# AC_v40.net
KiCad netlist of a schematic drawn in Altium Designer
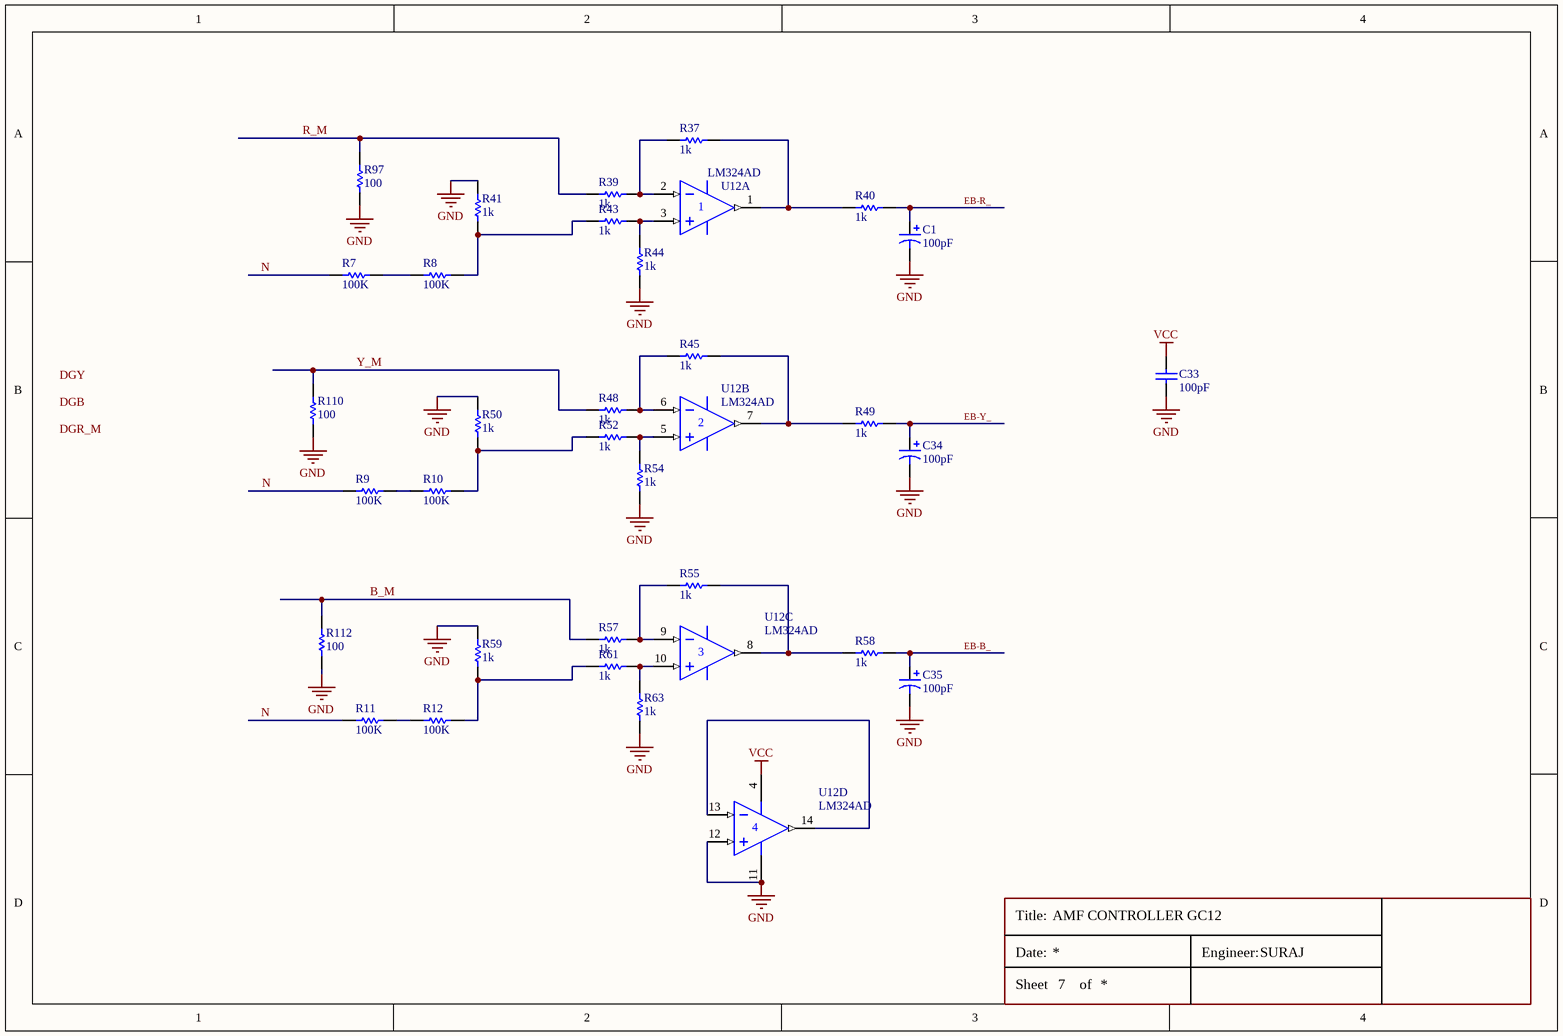
[diagram p0: AC_v40.SchDoc]

(export (version "E")
  (design (tool "Eeschema 10.0.6"))
  (components
    (comp (ref "C1")
      (value "100pF")
      (footprint "C1206")
      (description "Polarized Capacitor (Radial)")
      (fields (field (name "Comment") "10uF/63V") (field (name "PUBLISHER") "Altium Limited"))
      (libsource (lib "Miscellaneous Devices") (part "Cap Pol1"))
    )
    (comp (ref "C33")
      (value "100pF")
      (footprint "C1206")
      (description "Capacitor")
      (fields (field (name "Comment") ".1uF 1206") (field (name "PUBLISHER") "Altium Limited"))
      (libsource (lib "Miscellaneous Devices") (part "Cap"))
    )
    (comp (ref "C34")
      (value "100pF")
      (footprint "C1206")
      (description "Polarized Capacitor (Radial)")
      (fields (field (name "Comment") "10uF/63V") (field (name "PUBLISHER") "Altium Limited"))
      (libsource (lib "Miscellaneous Devices") (part "Cap Pol1"))
    )
    (comp (ref "C35")
      (value "100pF")
      (footprint "C1206")
      (description "Polarized Capacitor (Radial)")
      (fields (field (name "Comment") "10uF/63V") (field (name "PUBLISHER") "Altium Limited"))
      (libsource (lib "Miscellaneous Devices") (part "Cap Pol1"))
    )
    (comp (ref "R7")
      (value "100K")
      (footprint "AXIAL-0.5")
      (description "Semiconductor Resistor")
      (fields (field (name "Comment") "MFR 1M .5W") (field (name "PUBLISHER") "Altium Limited"))
      (libsource (lib "Miscellaneous Devices") (part "Res Semi"))
    )
    (comp (ref "R8")
      (value "100K")
      (footprint "AXIAL-0.5")
      (description "Semiconductor Resistor")
      (fields (field (name "Comment") "MFR 1M .5W") (field (name "PUBLISHER") "Altium Limited"))
      (libsource (lib "Miscellaneous Devices") (part "Res Semi"))
    )
    (comp (ref "R9")
      (value "100K")
      (footprint "AXIAL-0.5")
      (description "Semiconductor Resistor")
      (fields (field (name "Comment") "MFR 1M .5W") (field (name "PUBLISHER") "Altium Limited"))
      (libsource (lib "Miscellaneous Devices") (part "Res Semi"))
    )
    (comp (ref "R10")
      (value "100K")
      (footprint "AXIAL-0.5")
      (description "Semiconductor Resistor")
      (fields (field (name "Comment") "MFR 1M .5W") (field (name "PUBLISHER") "Altium Limited"))
      (libsource (lib "Miscellaneous Devices") (part "Res Semi"))
    )
    (comp (ref "R11")
      (value "100K")
      (footprint "AXIAL-0.5")
      (description "Semiconductor Resistor")
      (fields (field (name "Comment") "MFR 1M .5W") (field (name "PUBLISHER") "Altium Limited"))
      (libsource (lib "Miscellaneous Devices") (part "Res Semi"))
    )
    (comp (ref "R12")
      (value "100K")
      (footprint "AXIAL-0.5")
      (description "Semiconductor Resistor")
      (fields (field (name "Comment") "MFR 1M .5W") (field (name "PUBLISHER") "Altium Limited"))
      (libsource (lib "Miscellaneous Devices") (part "Res Semi"))
    )
    (comp (ref "R37")
      (value "1k")
      (footprint "R1206")
      (description "Semiconductor Resistor")
      (fields (field (name "Comment") "1M 1206") (field (name "PUBLISHER") "Altium Limited"))
      (libsource (lib "Miscellaneous Devices") (part "Res Semi"))
    )
    (comp (ref "R39")
      (value "1k")
      (footprint "R1206")
      (description "Semiconductor Resistor")
      (fields (field (name "Comment") "220K 1206") (field (name "PUBLISHER") "Altium Limited"))
      (libsource (lib "Miscellaneous Devices") (part "Res Semi"))
    )
    (comp (ref "R40")
      (value "1k")
      (footprint "R1206")
      (description "Semiconductor Resistor")
      (fields (field (name "Comment") "33K 1206") (field (name "PUBLISHER") "Altium Limited"))
      (libsource (lib "Miscellaneous Devices") (part "Res Semi"))
    )
    (comp (ref "R41")
      (value "1k")
      (footprint "R1206")
      (description "Semiconductor Resistor")
      (fields (field (name "Comment") "4.7K 1206") (field (name "PUBLISHER") "Altium Limited"))
      (libsource (lib "Miscellaneous Devices") (part "Res Semi"))
    )
    (comp (ref "R43")
      (value "1k")
      (footprint "r1206")
      (description "Semiconductor Resistor")
      (fields (field (name "Comment") "220K 1206") (field (name "PUBLISHER") "Altium Limited"))
      (libsource (lib "Miscellaneous Devices") (part "Res Semi"))
    )
    (comp (ref "R44")
      (value "1k")
      (footprint "R1206")
      (description "Semiconductor Resistor")
      (fields (field (name "Comment") "1M 1206") (field (name "PUBLISHER") "Altium Limited"))
      (libsource (lib "Miscellaneous Devices") (part "Res Semi"))
    )
    (comp (ref "R45")
      (value "1k")
      (footprint "R1206")
      (description "Semiconductor Resistor")
      (fields (field (name "Comment") "1M 1206") (field (name "PUBLISHER") "Altium Limited"))
      (libsource (lib "Miscellaneous Devices") (part "Res Semi"))
    )
    (comp (ref "R48")
      (value "1k")
      (footprint "R1206")
      (description "Semiconductor Resistor")
      (fields (field (name "Comment") "220K 1206") (field (name "PUBLISHER") "Altium Limited"))
      (libsource (lib "Miscellaneous Devices") (part "Res Semi"))
    )
    (comp (ref "R49")
      (value "1k")
      (footprint "R1206")
      (description "Semiconductor Resistor")
      (fields (field (name "Comment") "33K 1206") (field (name "PUBLISHER") "Altium Limited"))
      (libsource (lib "Miscellaneous Devices") (part "Res Semi"))
    )
    (comp (ref "R50")
      (value "1k")
      (footprint "R1206")
      (description "Semiconductor Resistor")
      (fields (field (name "Comment") "4.7K 1206") (field (name "PUBLISHER") "Altium Limited"))
      (libsource (lib "Miscellaneous Devices") (part "Res Semi"))
    )
    (comp (ref "R52")
      (value "1k")
      (footprint "R1206")
      (description "Semiconductor Resistor")
      (fields (field (name "Comment") "220K 1206") (field (name "PUBLISHER") "Altium Limited"))
      (libsource (lib "Miscellaneous Devices") (part "Res Semi"))
    )
    (comp (ref "R54")
      (value "1k")
      (footprint "R1206")
      (description "Semiconductor Resistor")
      (fields (field (name "Comment") "1M 1206") (field (name "PUBLISHER") "Altium Limited"))
      (libsource (lib "Miscellaneous Devices") (part "Res Semi"))
    )
    (comp (ref "R55")
      (value "1k")
      (footprint "R1206")
      (description "Semiconductor Resistor")
      (fields (field (name "Comment") "1M 1206") (field (name "PUBLISHER") "Altium Limited"))
      (libsource (lib "Miscellaneous Devices") (part "Res Semi"))
    )
    (comp (ref "R57")
      (value "1k")
      (footprint "R1206")
      (description "Semiconductor Resistor")
      (fields (field (name "Comment") "220K 1206") (field (name "PUBLISHER") "Altium Limited"))
      (libsource (lib "Miscellaneous Devices") (part "Res Semi"))
    )
    (comp (ref "R58")
      (value "1k")
      (footprint "R1206")
      (description "Semiconductor Resistor")
      (fields (field (name "Comment") "33K 1206") (field (name "PUBLISHER") "Altium Limited"))
      (libsource (lib "Miscellaneous Devices") (part "Res Semi"))
    )
    (comp (ref "R59")
      (value "1k")
      (footprint "R1206")
      (description "Semiconductor Resistor")
      (fields (field (name "Comment") "4.7K 1206") (field (name "PUBLISHER") "Altium Limited"))
      (libsource (lib "Miscellaneous Devices") (part "Res Semi"))
    )
    (comp (ref "R61")
      (value "1k")
      (footprint "R1206")
      (description "Semiconductor Resistor")
      (fields (field (name "Comment") "220K 1206") (field (name "PUBLISHER") "Altium Limited"))
      (libsource (lib "Miscellaneous Devices") (part "Res Semi"))
    )
    (comp (ref "R63")
      (value "1k")
      (footprint "R1206")
      (description "Semiconductor Resistor")
      (fields (field (name "Comment") "1M 1206") (field (name "PUBLISHER") "Altium Limited"))
      (libsource (lib "Miscellaneous Devices") (part "Res Semi"))
    )
    (comp (ref "R97")
      (value "100")
      (footprint "R1206")
      (description "Semiconductor Resistor")
      (fields (field (name "Comment") "4.7K 1206") (field (name "PUBLISHER") "Altium Limited"))
      (libsource (lib "Miscellaneous Devices") (part "Res Semi"))
    )
    (comp (ref "R110")
      (value "100")
      (footprint "R1206")
      (description "Semiconductor Resistor")
      (fields (field (name "Comment") "4.7K 1206") (field (name "PUBLISHER") "Altium Limited"))
      (libsource (lib "Miscellaneous Devices") (part "Res Semi"))
    )
    (comp (ref "R112")
      (value "100")
      (footprint "R1206")
      (description "Semiconductor Resistor")
      (fields (field (name "Comment") "4.7K 1206") (field (name "PUBLISHER") "Altium Limited"))
      (libsource (lib "Miscellaneous Devices") (part "Res Semi"))
    )
    (comp (ref "U12")
      (value "LM324AD")
      (footprint "D014_M")
      (description "Quadruple Operational Amplifier")
      (fields (field (name "PUBLISHER") "Altium Limited"))
      (libsource (lib "TI Operational Amplifier") (part "LM324AD"))
    )
  )
  (nets
    (net (code "1") (name "/B_M") (class "Default")
      (node (ref "R112") (pin "2") (pinfunction "2_2") (pintype "passive"))
      (node (ref "R57") (pin "2") (pinfunction "2_2") (pintype "passive"))
    )
    (net (code "5") (name "/EB-B_") (class "Default")
      (node (ref "C35") (pin "1") (pinfunction "1_1") (pintype "passive"))
      (node (ref "R58") (pin "1") (pinfunction "1_1") (pintype "passive"))
    )
    (net (code "6") (name "/EB-R_") (class "Default")
      (node (ref "C1") (pin "1") (pinfunction "1_1") (pintype "passive"))
      (node (ref "R40") (pin "1") (pinfunction "1_1") (pintype "passive"))
    )
    (net (code "7") (name "/EB-Y_") (class "Default")
      (node (ref "C34") (pin "1") (pinfunction "1_1") (pintype "passive"))
      (node (ref "R49") (pin "1") (pinfunction "1_1") (pintype "passive"))
    )
    (net (code "8") (name "/N") (class "Default")
      (node (ref "R11") (pin "1") (pinfunction "1_1") (pintype "passive"))
      (node (ref "R7") (pin "1") (pinfunction "1_1") (pintype "passive"))
      (node (ref "R9") (pin "1") (pinfunction "1_1") (pintype "passive"))
    )
    (net (code "9") (name "/R_M") (class "Default")
      (node (ref "R39") (pin "2") (pinfunction "2_2") (pintype "passive"))
      (node (ref "R97") (pin "2") (pinfunction "2_2") (pintype "passive"))
    )
    (net (code "10") (name "/Y_M") (class "Default")
      (node (ref "R110") (pin "2") (pinfunction "2_2") (pintype "passive"))
      (node (ref "R48") (pin "2") (pinfunction "2_2") (pintype "passive"))
    )
    (net (code "11") (name "GND") (class "Default")
      (node (ref "C1") (pin "2") (pinfunction "2_2") (pintype "passive"))
      (node (ref "C33") (pin "1") (pinfunction "1_1") (pintype "passive"))
      (node (ref "C34") (pin "2") (pinfunction "2_2") (pintype "passive"))
      (node (ref "C35") (pin "2") (pinfunction "2_2") (pintype "passive"))
      (node (ref "R110") (pin "1") (pinfunction "1_1") (pintype "passive"))
      (node (ref "R112") (pin "1") (pinfunction "1_1") (pintype "passive"))
      (node (ref "R41") (pin "2") (pinfunction "2_2") (pintype "passive"))
      (node (ref "R44") (pin "1") (pinfunction "1_1") (pintype "passive"))
      (node (ref "R50") (pin "2") (pinfunction "2_2") (pintype "passive"))
      (node (ref "R54") (pin "1") (pinfunction "1_1") (pintype "passive"))
      (node (ref "R59") (pin "2") (pinfunction "2_2") (pintype "passive"))
      (node (ref "R63") (pin "1") (pinfunction "1_1") (pintype "passive"))
      (node (ref "R97") (pin "1") (pinfunction "1_1") (pintype "passive"))
      (node (ref "U12") (pin "11") (pinfunction "V-_11") (pintype "power_in"))
      (node (ref "U12") (pin "12") (pinfunction "IN+_12") (pintype "input"))
    )
    (net (code "12") (name "Net-(R7-Pad2)") (class "Default")
      (node (ref "R7") (pin "2") (pinfunction "2_2") (pintype "passive"))
      (node (ref "R8") (pin "1") (pinfunction "1_1") (pintype "passive"))
    )
    (net (code "13") (name "Net-(R10-Pad1)") (class "Default")
      (node (ref "R10") (pin "1") (pinfunction "1_1") (pintype "passive"))
      (node (ref "R9") (pin "2") (pinfunction "2_2") (pintype "passive"))
    )
    (net (code "14") (name "Net-(R10-Pad2)") (class "Default")
      (node (ref "R10") (pin "2") (pinfunction "2_2") (pintype "passive"))
      (node (ref "R50") (pin "1") (pinfunction "1_1") (pintype "passive"))
      (node (ref "R52") (pin "2") (pinfunction "2_2") (pintype "passive"))
    )
    (net (code "15") (name "Net-(R11-Pad2)") (class "Default")
      (node (ref "R11") (pin "2") (pinfunction "2_2") (pintype "passive"))
      (node (ref "R12") (pin "1") (pinfunction "1_1") (pintype "passive"))
    )
    (net (code "16") (name "Net-(R12-Pad2)") (class "Default")
      (node (ref "R12") (pin "2") (pinfunction "2_2") (pintype "passive"))
      (node (ref "R59") (pin "1") (pinfunction "1_1") (pintype "passive"))
      (node (ref "R61") (pin "2") (pinfunction "2_2") (pintype "passive"))
    )
    (net (code "17") (name "Net-(R41-Pad1)") (class "Default")
      (node (ref "R41") (pin "1") (pinfunction "1_1") (pintype "passive"))
      (node (ref "R43") (pin "2") (pinfunction "2_2") (pintype "passive"))
      (node (ref "R8") (pin "2") (pinfunction "2_2") (pintype "passive"))
    )
    (net (code "18") (name "Net-(U12A-IN+)") (class "Default")
      (node (ref "R43") (pin "1") (pinfunction "1_1") (pintype "passive"))
      (node (ref "R44") (pin "2") (pinfunction "2_2") (pintype "passive"))
      (node (ref "U12") (pin "3") (pinfunction "IN+_3") (pintype "input"))
    )
    (net (code "19") (name "Net-(U12A-IN-)") (class "Default")
      (node (ref "R37") (pin "2") (pinfunction "2_2") (pintype "passive"))
      (node (ref "R39") (pin "1") (pinfunction "1_1") (pintype "passive"))
      (node (ref "U12") (pin "2") (pinfunction "IN-_2") (pintype "input"))
    )
    (net (code "20") (name "Net-(U12A-OUT)") (class "Default")
      (node (ref "R37") (pin "1") (pinfunction "1_1") (pintype "passive"))
      (node (ref "R40") (pin "2") (pinfunction "2_2") (pintype "passive"))
      (node (ref "U12") (pin "1") (pinfunction "OUT_1") (pintype "output"))
    )
    (net (code "21") (name "Net-(U12B-IN+)") (class "Default")
      (node (ref "R52") (pin "1") (pinfunction "1_1") (pintype "passive"))
      (node (ref "R54") (pin "2") (pinfunction "2_2") (pintype "passive"))
      (node (ref "U12") (pin "5") (pinfunction "IN+_5") (pintype "input"))
    )
    (net (code "22") (name "Net-(U12B-IN-)") (class "Default")
      (node (ref "R45") (pin "2") (pinfunction "2_2") (pintype "passive"))
      (node (ref "R48") (pin "1") (pinfunction "1_1") (pintype "passive"))
      (node (ref "U12") (pin "6") (pinfunction "IN-_6") (pintype "input"))
    )
    (net (code "23") (name "Net-(U12B-OUT)") (class "Default")
      (node (ref "R45") (pin "1") (pinfunction "1_1") (pintype "passive"))
      (node (ref "R49") (pin "2") (pinfunction "2_2") (pintype "passive"))
      (node (ref "U12") (pin "7") (pinfunction "OUT_7") (pintype "output"))
    )
    (net (code "24") (name "Net-(U12C-IN+)") (class "Default")
      (node (ref "R61") (pin "1") (pinfunction "1_1") (pintype "passive"))
      (node (ref "R63") (pin "2") (pinfunction "2_2") (pintype "passive"))
      (node (ref "U12") (pin "10") (pinfunction "IN+_10") (pintype "input"))
    )
    (net (code "25") (name "Net-(U12C-IN-)") (class "Default")
      (node (ref "R55") (pin "2") (pinfunction "2_2") (pintype "passive"))
      (node (ref "R57") (pin "1") (pinfunction "1_1") (pintype "passive"))
      (node (ref "U12") (pin "9") (pinfunction "IN-_9") (pintype "input"))
    )
    (net (code "26") (name "Net-(U12C-OUT)") (class "Default")
      (node (ref "R55") (pin "1") (pinfunction "1_1") (pintype "passive"))
      (node (ref "R58") (pin "2") (pinfunction "2_2") (pintype "passive"))
      (node (ref "U12") (pin "8") (pinfunction "OUT_8") (pintype "output"))
    )
    (net (code "27") (name "Net-(U12D-IN-)") (class "Default")
      (node (ref "U12") (pin "13") (pinfunction "IN-_13") (pintype "input"))
      (node (ref "U12") (pin "14") (pinfunction "OUT_14") (pintype "output"))
    )
    (net (code "28") (name "VCC") (class "Default")
      (node (ref "C33") (pin "2") (pinfunction "2_2") (pintype "passive"))
      (node (ref "U12") (pin "4") (pinfunction "V+_4") (pintype "power_in"))
    )
    (net (code "29") (name "unconnected-(U12A-V+-Pad4)") (class "Default")
      (node (ref "U12") (pin "4") (pinfunction "V+_4") (pintype "power_in"))
    )
    (net (code "30") (name "unconnected-(U12A-V--Pad11)") (class "Default")
      (node (ref "U12") (pin "11") (pinfunction "V-_11") (pintype "power_in"))
    )
    (net (code "31") (name "unconnected-(U12B-V+-Pad4)") (class "Default")
      (node (ref "U12") (pin "4") (pinfunction "V+_4") (pintype "power_in"))
    )
    (net (code "32") (name "unconnected-(U12B-V--Pad11)") (class "Default")
      (node (ref "U12") (pin "11") (pinfunction "V-_11") (pintype "power_in"))
    )
    (net (code "33") (name "unconnected-(U12C-V+-Pad4)") (class "Default")
      (node (ref "U12") (pin "4") (pinfunction "V+_4") (pintype "power_in"))
    )
    (net (code "34") (name "unconnected-(U12C-V--Pad11)") (class "Default")
      (node (ref "U12") (pin "11") (pinfunction "V-_11") (pintype "power_in"))
    )
  )
)
